# SCH_NFC-business-card_2025-08-06.net
KiCad netlist of a schematic drawn in EasyEDA
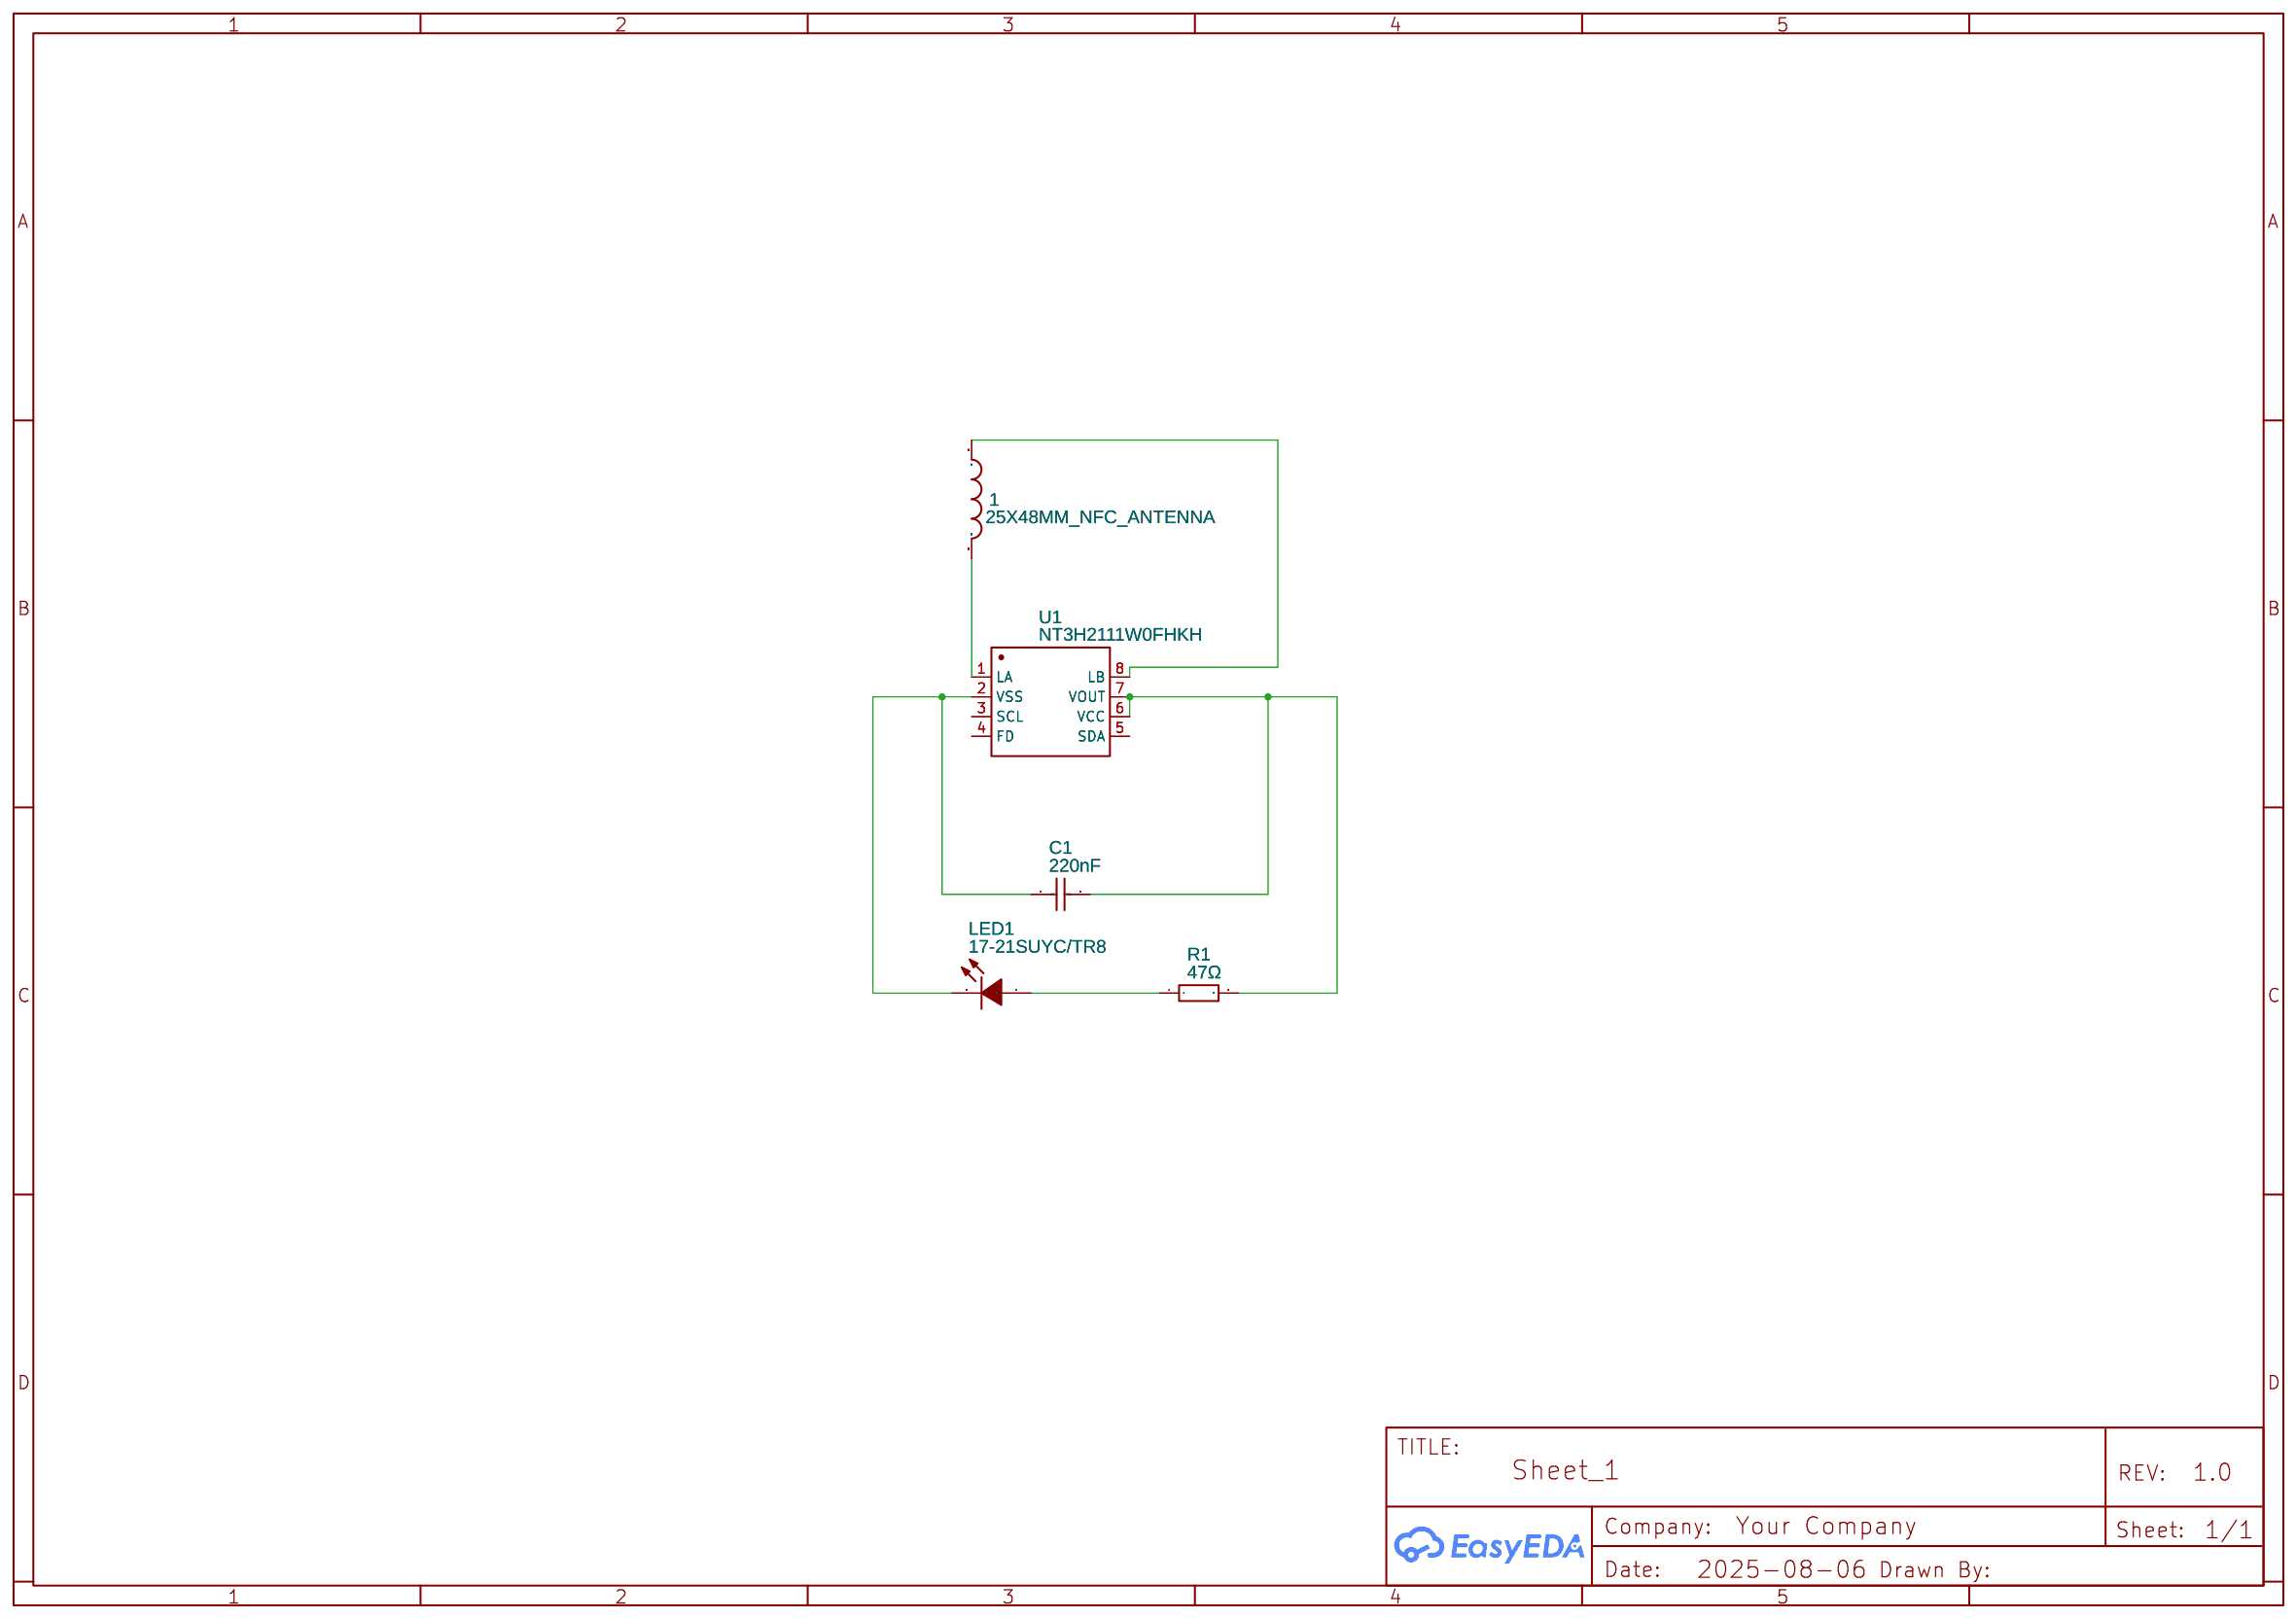
[diagram p0: schematic sheet]

(export (version "E")
  (design (tool "Eeschema 10.0.6"))
  (components
    (comp (ref "1") (value "25X48MM_NFC_ANTENNA") (libsource (lib "") (part "25X48MM_NFC_ANTENNA")))
    (comp (ref "C1")
      (value "220nF")
      (fields
        (field (name "Manufacturer Part") "CL10B224KA8NNNC")
        (field (name "Manufacturer") "SAMSUNG(三星)")
      )
      (libsource (lib "") (part "CL10B224KA8NNNC"))
    )
    (comp (ref "LED1")
      (value "17-21SUYC/TR8")
      (fields (field (name "Manufacturer Part") "KT-0805黄灯") (field (name "Manufacturer") "KENTO"))
      (libsource (lib "") (part "17-21SUYC/TR8"))
    )
    (comp (ref "R1")
      (value "47Ω")
      (fields
        (field (name "Manufacturer Part") "0603WAF470JT5E")
        (field (name "Manufacturer") "UNI-ROYAL(厚声)")
      )
      (libsource (lib "") (part "0603WAF470JT5E"))
    )
    (comp (ref "U1")
      (value "NT3H2111W0FHKH")
      (fields (field (name "Manufacturer") "NXP(恩智浦)"))
      (libsource (lib "") (part "NT3H2111W0FHKH"))
    )
  )
  (nets
    (net (code "1") (name "Net-(LED1-+)") (class "Default")
      (node (ref "LED1") (pin "1") (pinfunction "+_1") (pintype "unspecified"))
      (node (ref "R1") (pin "1") (pinfunction "1_1") (pintype "input"))
    )
    (net (code "2") (name "Net-(LED1--)") (class "Default")
      (node (ref "C1") (pin "1") (pinfunction "1_1") (pintype "input"))
      (node (ref "LED1") (pin "2") (pinfunction "-_2") (pintype "unspecified"))
      (node (ref "U1") (pin "2") (pinfunction "VSS_2") (pintype "unspecified"))
    )
    (net (code "3") (name "Net-(U1-LA)") (class "Default")
      (node (ref "1") (pin "P$2") (pinfunction "P$2_P$2") (pintype "bidirectional"))
      (node (ref "U1") (pin "1") (pinfunction "LA_1") (pintype "unspecified"))
    )
    (net (code "4") (name "Net-(U1-LB)") (class "Default")
      (node (ref "1") (pin "P$1") (pinfunction "P$1_P$1") (pintype "bidirectional"))
      (node (ref "U1") (pin "8") (pinfunction "LB_8") (pintype "unspecified"))
    )
    (net (code "5") (name "Net-(U1-VCC)") (class "Default")
      (node (ref "C1") (pin "2") (pinfunction "2_2") (pintype "input"))
      (node (ref "R1") (pin "2") (pinfunction "2_2") (pintype "input"))
      (node (ref "U1") (pin "6") (pinfunction "VCC_6") (pintype "unspecified"))
      (node (ref "U1") (pin "7") (pinfunction "VOUT_7") (pintype "unspecified"))
    )
    (net (code "6") (name "unconnected-(U1-FD-Pad4)") (class "Default")
      (node (ref "U1") (pin "4") (pinfunction "FD_4") (pintype "unspecified"))
    )
    (net (code "7") (name "unconnected-(U1-SCL-Pad3)") (class "Default")
      (node (ref "U1") (pin "3") (pinfunction "SCL_3") (pintype "unspecified"))
    )
    (net (code "8") (name "unconnected-(U1-SDA-Pad5)") (class "Default")
      (node (ref "U1") (pin "5") (pinfunction "SDA_5") (pintype "unspecified"))
    )
  )
)
